# MQ-2_SCH.net
KiCad netlist of a schematic drawn in Altium Designer
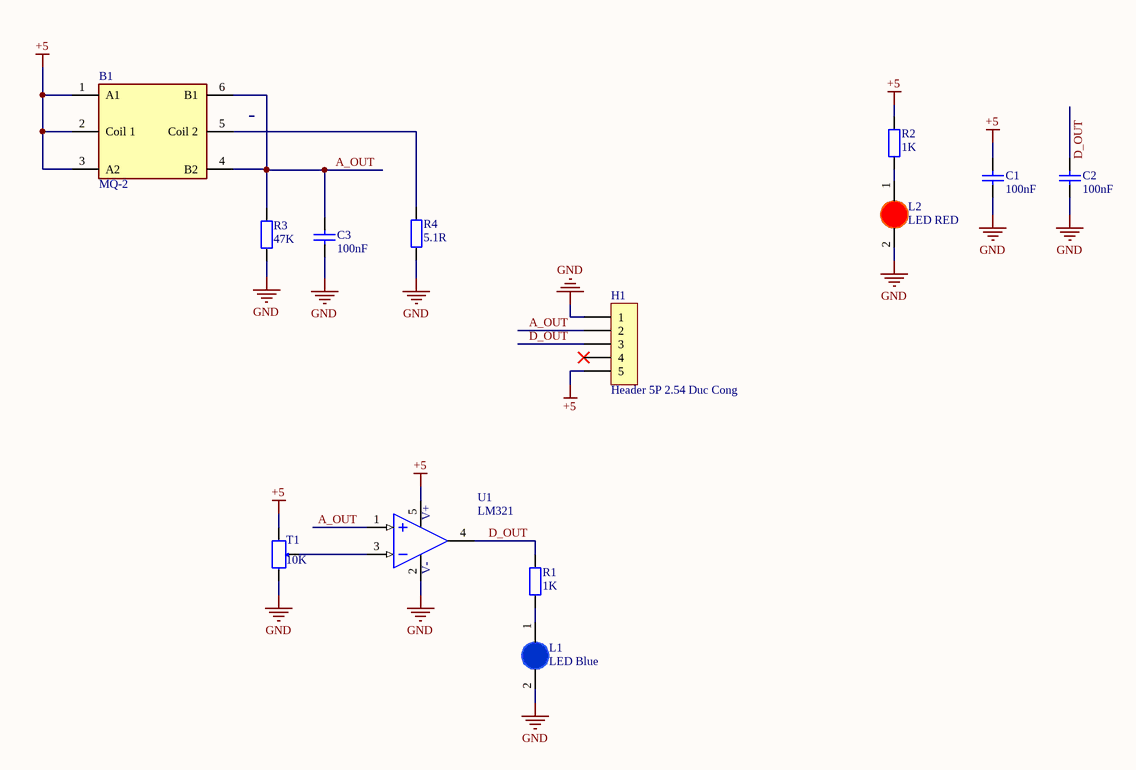
[diagram p0: MQ-2_SCH.SchDoc]

(export (version "E")
  (design (tool "Eeschema 10.0.6"))
  (components
    (comp (ref "B1")
      (value "MQ-2")
      (footprint "MQ2")
      (description "Sensor: gas; smoke,combustible gases; Range: 30010000ppm; MQ-2")
      (libsource (lib "namnt_Lib") (part "MQ-2"))
    )
    (comp (ref "C1")
      (value "100nF")
      (footprint "tu 0603")
      (description "Dán")
      (libsource (lib "namnt_Lib") (part "Tu 0603 104 50V 10%"))
    )
    (comp (ref "C2")
      (value "100nF")
      (footprint "tu 0603")
      (description "Dán")
      (libsource (lib "namnt_Lib") (part "Tu 0603 104 50V 10%"))
    )
    (comp (ref "C3")
      (value "100nF")
      (footprint "tu 0603")
      (description "Dán")
      (libsource (lib "namnt_Lib") (part "Tu 0603 104 50V 10%"))
    )
    (comp (ref "H1")
      (value "Header 5P 2.54 Duc Cong")
      (footprint "Header 5P DC 2.54")
      (description "Cắm")
      (libsource (lib "namnt_Lib") (part "Header 5P 2.54 Duc Cong"))
    )
    (comp (ref "L1")
      (value "LED Blue")
      (footprint "LED-0805-Blue")
      (description "Dán")
      (libsource (lib "namnt_Lib") (part "LED 0805 Xanh Duong"))
    )
    (comp (ref "L2")
      (value "LED RED")
      (footprint "LED-0805-Red")
      (description "Dán")
      (libsource (lib "namnt_Lib") (part "LED 0805 Do"))
    )
    (comp (ref "R1")
      (value "1K")
      (footprint "tro smd 0603")
      (description "Dán")
      (libsource (lib "namnt_Lib") (part "Tro 0603 1% 1k"))
    )
    (comp (ref "R2")
      (value "1K")
      (footprint "tro smd 0603")
      (description "Dán")
      (libsource (lib "namnt_Lib") (part "Tro 0603 1% 1k"))
    )
    (comp (ref "R3")
      (value "47K")
      (footprint "tro smd 0603")
      (description "Dán")
      (libsource (lib "namnt_Lib") (part "Tro 0603 5% 47k"))
    )
    (comp (ref "R4")
      (value "5.1R")
      (footprint "tro smd 0603")
      (description "Dán")
      (libsource (lib "namnt_Lib") (part "Tro 0603 5% 47k"))
    )
    (comp (ref "T1")
      (value "10K")
      (footprint "Bien Tro Vi Chinh Dung")
      (description "Cắm")
      (libsource (lib "namnt_Lib") (part "Bien Tro Tinh Chinh 10K Dung"))
    )
    (comp (ref "U1")
      (value "LM321")
      (footprint "xlib:sot23-5")
      (description "Opamp")
      (libsource (lib "XLib") (part "LM321"))
    )
  )
  (nets
    (net (code "1") (name "+5") (class "Default")
      (node (ref "B1") (pin "1") (pinfunction "A1_1") (pintype "passive"))
      (node (ref "B1") (pin "2") (pinfunction "Coil_1_2") (pintype "passive"))
      (node (ref "B1") (pin "3") (pinfunction "A2_3") (pintype "passive"))
      (node (ref "C1") (pin "1") (pinfunction "1_1") (pintype "passive"))
      (node (ref "H1") (pin "5") (pinfunction "5_5") (pintype "passive"))
      (node (ref "R2") (pin "2") (pinfunction "2_2") (pintype "passive"))
      (node (ref "T1") (pin "3") (pinfunction "3_3") (pintype "passive"))
      (node (ref "U1") (pin "5") (pinfunction "V+_5") (pintype "power_in"))
    )
    (net (code "2") (name "/A_OUT") (class "Default")
      (node (ref "B1") (pin "4") (pinfunction "B2_4") (pintype "passive"))
      (node (ref "B1") (pin "6") (pinfunction "B1_6") (pintype "passive"))
      (node (ref "C3") (pin "1") (pinfunction "1_1") (pintype "passive"))
      (node (ref "H1") (pin "2") (pinfunction "2_2") (pintype "passive"))
      (node (ref "R3") (pin "2") (pinfunction "2_2") (pintype "passive"))
      (node (ref "U1") (pin "1") (pinfunction "IN+_1") (pintype "input"))
    )
    (net (code "3") (name "/D_OUT") (class "Default")
      (node (ref "C2") (pin "1") (pinfunction "1_1") (pintype "passive"))
      (node (ref "H1") (pin "3") (pinfunction "3_3") (pintype "passive"))
      (node (ref "R1") (pin "2") (pinfunction "2_2") (pintype "passive"))
      (node (ref "U1") (pin "4") (pinfunction "-V_4") (pintype "passive"))
    )
    (net (code "4") (name "GND") (class "Default")
      (node (ref "C1") (pin "2") (pinfunction "2_2") (pintype "passive"))
      (node (ref "C2") (pin "2") (pinfunction "2_2") (pintype "passive"))
      (node (ref "C3") (pin "2") (pinfunction "2_2") (pintype "passive"))
      (node (ref "H1") (pin "1") (pinfunction "1_1") (pintype "passive"))
      (node (ref "L1") (pin "2") (pinfunction "K_2") (pintype "passive"))
      (node (ref "L2") (pin "2") (pinfunction "K_2") (pintype "passive"))
      (node (ref "R3") (pin "1") (pinfunction "1_1") (pintype "passive"))
      (node (ref "R4") (pin "1") (pinfunction "1_1") (pintype "passive"))
      (node (ref "T1") (pin "1") (pinfunction "1_1") (pintype "passive"))
      (node (ref "U1") (pin "2") (pinfunction "V-_2") (pintype "power_in"))
    )
    (net (code "5") (name "Net-(B1-Coil_2)") (class "Default")
      (node (ref "B1") (pin "5") (pinfunction "Coil_2_5") (pintype "passive"))
      (node (ref "R4") (pin "2") (pinfunction "2_2") (pintype "passive"))
    )
    (net (code "6") (name "Net-(L1-A)") (class "Default")
      (node (ref "L1") (pin "1") (pinfunction "A_1") (pintype "passive"))
      (node (ref "R1") (pin "1") (pinfunction "1_1") (pintype "passive"))
    )
    (net (code "7") (name "Net-(L2-A)") (class "Default")
      (node (ref "L2") (pin "1") (pinfunction "A_1") (pintype "passive"))
      (node (ref "R2") (pin "1") (pinfunction "1_1") (pintype "passive"))
    )
    (net (code "8") (name "Net-(U1-IN-)") (class "Default")
      (node (ref "T1") (pin "2") (pinfunction "2_2") (pintype "passive"))
      (node (ref "U1") (pin "3") (pinfunction "IN-_3") (pintype "input"))
    )
    (net (code "9") (name "unconnected-(H1-Pad4)") (class "Default")
      (node (ref "H1") (pin "4") (pinfunction "4_4") (pintype "passive+no_connect"))
    )
  )
)
